# CW308T_87C51_CPU.net
KiCad netlist of a schematic drawn in Altium Designer
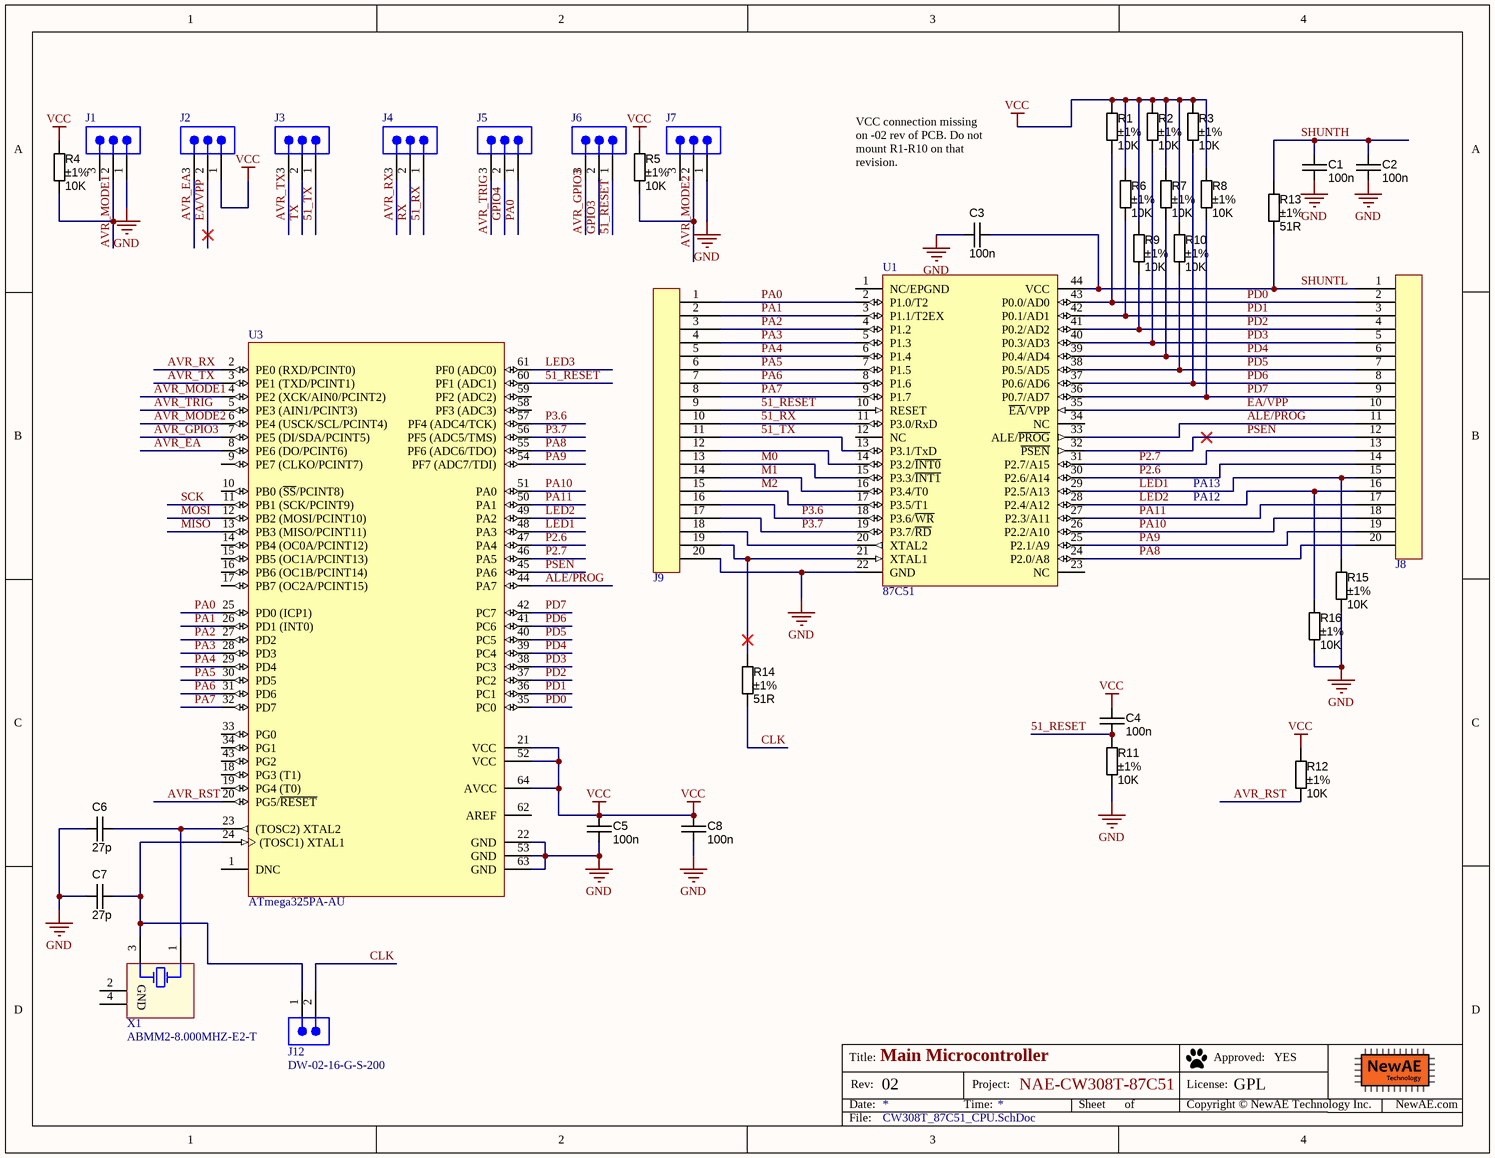
[diagram p0: CW308T_87C51_CPU.SchDoc]

(export (version "E")
  (design (tool "Eeschema 10.0.6"))
  (components
    (comp (ref "C1")
      (value "100n")
      (footprint "CAPC1608X90N")
      (description "Capacitor SMD Cer 100nF 10% 50V X7R 0603")
      (fields (field (name "TOLERANCE") "±10%") (field (name "Comment") "approved sub OK"))
      (libsource (lib "PBL - Capacitors") (part "CAPC_100n_0603_X7R_50V_10%"))
    )
    (comp (ref "C2")
      (value "100n")
      (footprint "CAPC1608X90N")
      (description "Capacitor SMD Cer 100nF 10% 50V X7R 0603")
      (fields (field (name "TOLERANCE") "±10%") (field (name "Comment") "approved sub OK"))
      (libsource (lib "PBL - Capacitors") (part "CAPC_100n_0603_X7R_50V_10%"))
    )
    (comp (ref "C3")
      (value "100n")
      (footprint "CAPC1608X90N")
      (description "Capacitor SMD Cer 100nF 10% 50V X7R 0603")
      (fields (field (name "TOLERANCE") "±10%") (field (name "Comment") "approved sub OK"))
      (libsource (lib "PBL - Capacitors") (part "CAPC_100n_0603_X7R_50V_10%"))
    )
    (comp (ref "C4")
      (value "100n")
      (footprint "CAPC1608X90N")
      (description "Capacitor SMD Cer 100nF 10% 50V X7R 0603")
      (fields (field (name "TOLERANCE") "±10%") (field (name "Comment") "approved sub OK"))
      (libsource (lib "PBL - Capacitors") (part "CAPC_100n_0603_X7R_50V_10%"))
    )
    (comp (ref "C5")
      (value "100n")
      (footprint "CAPC1608X90N")
      (description "Capacitor SMD Cer 100nF 10% 50V X7R 0603")
      (fields (field (name "TOLERANCE") "±10%") (field (name "Comment") "approved sub OK"))
      (libsource (lib "PBL - Capacitors") (part "CAPC_100n_0603_X7R_50V_10%"))
    )
    (comp (ref "C6")
      (value "27p")
      (footprint "CAPC1608X90N")
      (description "Capacitor SMD Cer 27pF 1% 100V NP0 0603")
      (fields (field (name "TOLERANCE") "±1%"))
      (libsource (lib "PBL - Capacitors") (part "CAPC_27p_0603_NP0_100V_1%"))
    )
    (comp (ref "C7")
      (value "27p")
      (footprint "CAPC1608X90N")
      (description "Capacitor SMD Cer 27pF 1% 100V NP0 0603")
      (fields (field (name "TOLERANCE") "±1%"))
      (libsource (lib "PBL - Capacitors") (part "CAPC_27p_0603_NP0_100V_1%"))
    )
    (comp (ref "C8")
      (value "100n")
      (footprint "CAPC1608X90N")
      (description "Capacitor SMD Cer 100nF 10% 50V X7R 0603")
      (fields (field (name "TOLERANCE") "±10%") (field (name "Comment") "approved sub OK"))
      (libsource (lib "PBL - Capacitors") (part "CAPC_100n_0603_X7R_50V_10%"))
    )
    (comp (ref "J1")
      (value "68000-203HLF")
      (footprint "SMTC-TSW-103-07-X-S")
      (fields (field (name "MANUFACTURER") "Samtec"))
      (libsource (lib "Altium Content Vault") (part "CMP-1024-00333-1"))
    )
    (comp (ref "J2")
      (value "68000-203HLF")
      (footprint "SMTC-TSW-103-07-X-S")
      (fields (field (name "MANUFACTURER") "Samtec"))
      (libsource (lib "Altium Content Vault") (part "CMP-1024-00333-1"))
    )
    (comp (ref "J3")
      (value "68000-203HLF")
      (footprint "SMTC-TSW-103-07-X-S")
      (fields (field (name "MANUFACTURER") "Samtec"))
      (libsource (lib "Altium Content Vault") (part "CMP-1024-00333-1"))
    )
    (comp (ref "J4")
      (value "68000-203HLF")
      (footprint "SMTC-TSW-103-07-X-S")
      (fields (field (name "MANUFACTURER") "Samtec"))
      (libsource (lib "Altium Content Vault") (part "CMP-1024-00333-1"))
    )
    (comp (ref "J5")
      (value "68000-203HLF")
      (footprint "SMTC-TSW-103-07-X-S")
      (fields (field (name "MANUFACTURER") "Samtec"))
      (libsource (lib "Altium Content Vault") (part "CMP-1024-00333-1"))
    )
    (comp (ref "J6")
      (value "68000-203HLF")
      (footprint "SMTC-TSW-103-07-X-S")
      (fields (field (name "MANUFACTURER") "Samtec"))
      (libsource (lib "Altium Content Vault") (part "CMP-1024-00333-1"))
    )
    (comp (ref "J7")
      (value "68000-203HLF")
      (footprint "SMTC-TSW-103-07-X-S")
      (fields (field (name "MANUFACTURER") "Samtec"))
      (libsource (lib "Altium Content Vault") (part "CMP-1024-00333-1"))
    )
    (comp (ref "J8")
      (value "20-Pin Header")
      (footprint "801-87-020-10-001101")
      (description "1x20 Header, Machined")
      (libsource (lib "NewAE_AltiumLib") (part "801-87-020-10-001101"))
    )
    (comp (ref "J9")
      (value "20-Pin Header")
      (footprint "801-87-020-10-001101")
      (description "1x20 Header, Machined")
      (libsource (lib "") (part "801-87-020-10-001101_1"))
    )
    (comp (ref "J12")
      (value "DW-02-16-G-S-200")
      (footprint "SMTC-DW-02-16-X-S-200")
      (fields (field (name "MANUFACTURER") "Samtec"))
      (libsource (lib "Altium Content Vault") (part "SMTC-DW-02-16-X-S-200"))
    )
    (comp (ref "R1")
      (value "10K")
      (footprint "RESC1608X55N")
      (description "Resistor SMD chip 10k Ohm 0.1W 1% 0603")
      (fields (field (name "TOLERANCE") "±1%") (field (name "Comment") "Thick Film"))
      (libsource (lib "PBL - Resistors") (part "RES_10K_0603_1%"))
    )
    (comp (ref "R2")
      (value "10K")
      (footprint "RESC1608X55N")
      (description "Resistor SMD chip 10k Ohm 0.1W 1% 0603")
      (fields (field (name "TOLERANCE") "±1%") (field (name "Comment") "Thick Film"))
      (libsource (lib "PBL - Resistors") (part "RES_10K_0603_1%"))
    )
    (comp (ref "R3")
      (value "10K")
      (footprint "RESC1608X55N")
      (description "Resistor SMD chip 10k Ohm 0.1W 1% 0603")
      (fields (field (name "TOLERANCE") "±1%") (field (name "Comment") "Thick Film"))
      (libsource (lib "PBL - Resistors") (part "RES_10K_0603_1%"))
    )
    (comp (ref "R4")
      (value "10K")
      (footprint "RESC1608X55N")
      (description "Resistor SMD chip 10k Ohm 0.1W 1% 0603")
      (fields (field (name "TOLERANCE") "±1%") (field (name "Comment") "Thick Film"))
      (libsource (lib "PBL - Resistors") (part "RES_10K_0603_1%"))
    )
    (comp (ref "R5")
      (value "10K")
      (footprint "RESC1608X55N")
      (description "Resistor SMD chip 10k Ohm 0.1W 1% 0603")
      (fields (field (name "TOLERANCE") "±1%") (field (name "Comment") "Thick Film"))
      (libsource (lib "") (part "RES_10K_0603_1%_1"))
    )
    (comp (ref "R6")
      (value "10K")
      (footprint "RESC1608X55N")
      (description "Resistor SMD chip 10k Ohm 0.1W 1% 0603")
      (fields (field (name "TOLERANCE") "±1%") (field (name "Comment") "Thick Film"))
      (libsource (lib "PBL - Resistors") (part "RES_10K_0603_1%"))
    )
    (comp (ref "R7")
      (value "10K")
      (footprint "RESC1608X55N")
      (description "Resistor SMD chip 10k Ohm 0.1W 1% 0603")
      (fields (field (name "TOLERANCE") "±1%") (field (name "Comment") "Thick Film"))
      (libsource (lib "PBL - Resistors") (part "RES_10K_0603_1%"))
    )
    (comp (ref "R8")
      (value "10K")
      (footprint "RESC1608X55N")
      (description "Resistor SMD chip 10k Ohm 0.1W 1% 0603")
      (fields (field (name "TOLERANCE") "±1%") (field (name "Comment") "Thick Film"))
      (libsource (lib "PBL - Resistors") (part "RES_10K_0603_1%"))
    )
    (comp (ref "R9")
      (value "10K")
      (footprint "RESC1608X55N")
      (description "Resistor SMD chip 10k Ohm 0.1W 1% 0603")
      (fields (field (name "TOLERANCE") "±1%") (field (name "Comment") "Thick Film"))
      (libsource (lib "PBL - Resistors") (part "RES_10K_0603_1%"))
    )
    (comp (ref "R10")
      (value "10K")
      (footprint "RESC1608X55N")
      (description "Resistor SMD chip 10k Ohm 0.1W 1% 0603")
      (fields (field (name "TOLERANCE") "±1%") (field (name "Comment") "Thick Film"))
      (libsource (lib "PBL - Resistors") (part "RES_10K_0603_1%"))
    )
    (comp (ref "R11")
      (value "10K")
      (footprint "RESC1608X55N")
      (description "Resistor SMD chip 10k Ohm 0.1W 1% 0603")
      (fields (field (name "TOLERANCE") "±1%") (field (name "Comment") "Thick Film"))
      (libsource (lib "PBL - Resistors") (part "RES_10K_0603_1%"))
    )
    (comp (ref "R12")
      (value "10K")
      (footprint "RESC1608X55N")
      (description "Resistor SMD chip 10k Ohm 0.1W 1% 0603")
      (fields (field (name "TOLERANCE") "±1%") (field (name "Comment") "Thick Film"))
      (libsource (lib "PBL - Resistors") (part "RES_10K_0603_1%"))
    )
    (comp (ref "R13")
      (value "51R")
      (footprint "RESC1608X55N")
      (description "Resistor SMD chip 51 Ohm 0.1W 1% 0603")
      (fields (field (name "TOLERANCE") "±1%") (field (name "Comment") "Thick Film"))
      (libsource (lib "PBL - Resistors") (part "RES_51R_0603_1%"))
    )
    (comp (ref "R14")
      (value "51R")
      (footprint "RESC1608X55N")
      (description "Resistor SMD chip 51 Ohm 0.1W 1% 0603")
      (fields (field (name "TOLERANCE") "±1%") (field (name "Comment") "Thick Film"))
      (libsource (lib "PBL - Resistors") (part "RES_51R_0603_1%"))
    )
    (comp (ref "R15")
      (value "10K")
      (footprint "RESC1608X55N")
      (description "Resistor SMD chip 10k Ohm 0.1W 1% 0603")
      (fields (field (name "TOLERANCE") "±1%") (field (name "Comment") "Thick Film"))
      (libsource (lib "PBL - Resistors") (part "RES_10K_0603_1%"))
    )
    (comp (ref "R16")
      (value "10K")
      (footprint "RESC1608X55N")
      (description "Resistor SMD chip 10k Ohm 0.1W 1% 0603")
      (fields (field (name "TOLERANCE") "±1%") (field (name "Comment") "Thick Film"))
      (libsource (lib "PBL - Resistors") (part "RES_10K_0603_1%"))
    )
    (comp (ref "U1")
      (value "87C51")
      (footprint "NewAE_AltiumLib:PLCC44_SOCKET")
      (libsource (lib "NewAE_AltiumLib") (part "87C51"))
    )
    (comp (ref "U3")
      (value "ATmega325PA-AU")
      (footprint "64A_M")
      (libsource (lib "Altium Content Vault") (part "MC-8B-ATM165-SQ64"))
    )
    (comp (ref "X1")
      (value "ABMM2-8.000MHZ-E2-T")
      (footprint "ABRA-ABMM2-4_V")
      (fields (field (name "MANUFACTURER") "Abracon"))
      (libsource (lib "Altium Content Vault") (part "ABRA-XTAL_1-3-4"))
    )
  )
  (nets
    (net (code "1") (name "/51_RESET") (class "Default")
      (node (ref "C4") (pin "2") (pintype "passive"))
      (node (ref "J6") (pin "1") (pinfunction "1_1") (pintype "passive"))
      (node (ref "J9") (pin "9") (pintype "passive"))
      (node (ref "R11") (pin "1") (pinfunction "1_1") (pintype "passive"))
      (node (ref "U1") (pin "10") (pinfunction "RESET_10") (pintype "input"))
      (node (ref "U3") (pin "60") (pinfunction "PF1_(ADC1)_60") (pintype "bidirectional"))
    )
    (net (code "2") (name "/51_RX") (class "Default")
      (node (ref "J4") (pin "1") (pinfunction "1_1") (pintype "passive"))
      (node (ref "J9") (pin "10") (pintype "passive"))
      (node (ref "U1") (pin "11") (pinfunction "P3.0/RxD_11") (pintype "bidirectional"))
    )
    (net (code "3") (name "/51_TX") (class "Default")
      (node (ref "J3") (pin "1") (pinfunction "1_1") (pintype "passive"))
      (node (ref "J9") (pin "11") (pintype "passive"))
      (node (ref "U1") (pin "13") (pinfunction "P3.1/TxD_13") (pintype "bidirectional"))
    )
    (net (code "4") (name "/ALE{slash}PROG") (class "Default")
      (node (ref "J8") (pin "11") (pintype "passive"))
      (node (ref "U1") (pin "33") (pinfunction "ALE/~{PROG}_33") (pintype "output"))
      (node (ref "U3") (pin "44") (pinfunction "PA7_44") (pintype "bidirectional"))
    )
    (net (code "5") (name "/AVR_EA") (class "Default")
      (node (ref "J2") (pin "3") (pinfunction "3_3") (pintype "passive"))
      (node (ref "U3") (pin "8") (pinfunction "PE6_(DO/PCINT6)_8") (pintype "bidirectional"))
    )
    (net (code "6") (name "/AVR_GPIO3") (class "Default")
      (node (ref "J6") (pin "3") (pinfunction "3_3") (pintype "passive"))
      (node (ref "U3") (pin "7") (pinfunction "PE5_(DI/SDA/PCINT5)_7") (pintype "bidirectional"))
    )
    (net (code "7") (name "/AVR_MODE1") (class "Default")
      (node (ref "J1") (pin "2") (pinfunction "2_2") (pintype "passive"))
      (node (ref "R4") (pin "2") (pinfunction "2_2") (pintype "passive"))
      (node (ref "U3") (pin "4") (pinfunction "PE2_(XCK/AIN0/PCINT2)_4") (pintype "bidirectional"))
    )
    (net (code "8") (name "/AVR_MODE2") (class "Default")
      (node (ref "J7") (pin "2") (pinfunction "2_2") (pintype "passive"))
      (node (ref "R5") (pin "1") (pinfunction "1_1") (pintype "passive"))
      (node (ref "U3") (pin "6") (pinfunction "PE4_(USCK/SCL/PCINT4)_6") (pintype "bidirectional"))
    )
    (net (code "9") (name "/AVR_RST") (class "Default")
      (node (ref "R12") (pin "2") (pinfunction "2_2") (pintype "passive"))
      (node (ref "U3") (pin "20") (pinfunction "PG5/~{RESET}_20") (pintype "bidirectional"))
    )
    (net (code "10") (name "/AVR_RX") (class "Default")
      (node (ref "J4") (pin "3") (pinfunction "3_3") (pintype "passive"))
      (node (ref "U3") (pin "2") (pinfunction "PE0_(RXD/PCINT0)_2") (pintype "bidirectional"))
    )
    (net (code "11") (name "/AVR_TRIG") (class "Default")
      (node (ref "J5") (pin "3") (pinfunction "3_3") (pintype "passive"))
      (node (ref "U3") (pin "5") (pinfunction "PE3_(AIN1/PCINT3)_5") (pintype "bidirectional"))
    )
    (net (code "12") (name "/AVR_TX") (class "Default")
      (node (ref "J3") (pin "3") (pinfunction "3_3") (pintype "passive"))
      (node (ref "U3") (pin "3") (pinfunction "PE1_(TXD/PCINT1)_3") (pintype "bidirectional"))
    )
    (net (code "13") (name "/CLK") (class "Default")
      (node (ref "J12") (pin "2") (pinfunction "2_2") (pintype "passive"))
      (node (ref "R14") (pin "2") (pinfunction "2_2") (pintype "passive"))
    )
    (net (code "14") (name "/EA{slash}VPP") (class "Default")
      (node (ref "J2") (pin "2") (pinfunction "2_2") (pintype "passive"))
      (node (ref "J8") (pin "10") (pintype "passive"))
      (node (ref "U1") (pin "35") (pinfunction "~{EA}/VPP_35") (pintype "input"))
    )
    (net (code "15") (name "/GPIO3") (class "Default")
      (node (ref "J6") (pin "2") (pinfunction "2_2") (pintype "passive"))
    )
    (net (code "16") (name "/GPIO4") (class "Default")
      (node (ref "J5") (pin "2") (pinfunction "2_2") (pintype "passive"))
    )
    (net (code "17") (name "/LED1") (class "Default")
      (node (ref "J8") (pin "15") (pintype "passive"))
      (node (ref "R15") (pin "1") (pinfunction "1_1") (pintype "passive"))
      (node (ref "U1") (pin "29") (pinfunction "P2.5/A13_29") (pintype "bidirectional"))
      (node (ref "U3") (pin "48") (pinfunction "PA3_48") (pintype "bidirectional"))
    )
    (net (code "18") (name "/LED2") (class "Default")
      (node (ref "J8") (pin "16") (pintype "passive"))
      (node (ref "R16") (pin "1") (pinfunction "1_1") (pintype "passive"))
      (node (ref "U1") (pin "28") (pinfunction "P2.4/A12_28") (pintype "bidirectional"))
      (node (ref "U3") (pin "49") (pinfunction "PA2_49") (pintype "bidirectional"))
    )
    (net (code "19") (name "/LED3") (class "Default")
      (node (ref "U3") (pin "61") (pinfunction "PF0_(ADC0)_61") (pintype "bidirectional"))
    )
    (net (code "20") (name "/M0") (class "Default")
      (node (ref "J9") (pin "13") (pintype "passive"))
      (node (ref "U1") (pin "15") (pinfunction "P3.3/~{INT1}_15") (pintype "bidirectional"))
    )
    (net (code "21") (name "/M1") (class "Default")
      (node (ref "J9") (pin "14") (pintype "passive"))
      (node (ref "U1") (pin "16") (pinfunction "P3.4/T0_16") (pintype "bidirectional"))
    )
    (net (code "22") (name "/M2") (class "Default")
      (node (ref "J9") (pin "15") (pintype "passive"))
      (node (ref "U1") (pin "17") (pinfunction "P3.5/T1_17") (pintype "bidirectional"))
    )
    (net (code "23") (name "/MISO") (class "Default")
      (node (ref "U3") (pin "13") (pinfunction "PB3_(MISO/PCINT11)_13") (pintype "bidirectional"))
    )
    (net (code "24") (name "/MOSI") (class "Default")
      (node (ref "U3") (pin "12") (pinfunction "PB2_(MOSI/PCINT10)_12") (pintype "bidirectional"))
    )
    (net (code "25") (name "/P2.6") (class "Default")
      (node (ref "J8") (pin "14") (pintype "passive"))
      (node (ref "U1") (pin "30") (pinfunction "P2.6/A14_30") (pintype "bidirectional"))
      (node (ref "U3") (pin "47") (pinfunction "PA4_47") (pintype "bidirectional"))
    )
    (net (code "26") (name "/P2.7") (class "Default")
      (node (ref "J8") (pin "13") (pintype "passive"))
      (node (ref "U1") (pin "31") (pinfunction "P2.7/A15_31") (pintype "bidirectional"))
      (node (ref "U3") (pin "46") (pinfunction "PA5_46") (pintype "bidirectional"))
    )
    (net (code "27") (name "/P3.6") (class "Default")
      (node (ref "J9") (pin "16") (pintype "passive"))
      (node (ref "U1") (pin "18") (pinfunction "P3.6/~{WR}_18") (pintype "bidirectional"))
      (node (ref "U3") (pin "57") (pinfunction "PF4_(ADC4/TCK)_57") (pintype "bidirectional"))
    )
    (net (code "28") (name "/P3.7") (class "Default")
      (node (ref "J9") (pin "17") (pintype "passive"))
      (node (ref "U1") (pin "19") (pinfunction "P3.7/~{RD}_19") (pintype "bidirectional"))
      (node (ref "U3") (pin "56") (pinfunction "PF5_(ADC5/TMS)_56") (pintype "bidirectional"))
    )
    (net (code "29") (name "/PA0") (class "Default")
      (node (ref "J5") (pin "1") (pinfunction "1_1") (pintype "passive"))
      (node (ref "J9") (pin "1") (pintype "passive"))
      (node (ref "U1") (pin "2") (pinfunction "P1.0/T2_2") (pintype "bidirectional"))
      (node (ref "U3") (pin "25") (pinfunction "PD0_(ICP1)_25") (pintype "bidirectional"))
    )
    (net (code "30") (name "/PA1") (class "Default")
      (node (ref "J9") (pin "2") (pintype "passive"))
      (node (ref "U1") (pin "3") (pinfunction "P1.1/T2EX_3") (pintype "bidirectional"))
      (node (ref "U3") (pin "26") (pinfunction "PD1_(INT0)_26") (pintype "bidirectional"))
    )
    (net (code "31") (name "/PA2") (class "Default")
      (node (ref "J9") (pin "3") (pintype "passive"))
      (node (ref "U1") (pin "4") (pinfunction "P1.2_4") (pintype "bidirectional"))
      (node (ref "U3") (pin "27") (pinfunction "PD2_27") (pintype "bidirectional"))
    )
    (net (code "32") (name "/PA3") (class "Default")
      (node (ref "J9") (pin "4") (pintype "passive"))
      (node (ref "U1") (pin "5") (pinfunction "P1.3_5") (pintype "bidirectional"))
      (node (ref "U3") (pin "28") (pinfunction "PD3_28") (pintype "bidirectional"))
    )
    (net (code "33") (name "/PA4") (class "Default")
      (node (ref "J9") (pin "5") (pintype "passive"))
      (node (ref "U1") (pin "6") (pinfunction "P1.4_6") (pintype "bidirectional"))
      (node (ref "U3") (pin "29") (pinfunction "PD4_29") (pintype "bidirectional"))
    )
    (net (code "34") (name "/PA5") (class "Default")
      (node (ref "J9") (pin "6") (pintype "passive"))
      (node (ref "U1") (pin "7") (pinfunction "P1.5_7") (pintype "bidirectional"))
      (node (ref "U3") (pin "30") (pinfunction "PD5_30") (pintype "bidirectional"))
    )
    (net (code "35") (name "/PA6") (class "Default")
      (node (ref "J9") (pin "7") (pintype "passive"))
      (node (ref "U1") (pin "8") (pinfunction "P1.6_8") (pintype "bidirectional"))
      (node (ref "U3") (pin "31") (pinfunction "PD6_31") (pintype "bidirectional"))
    )
    (net (code "36") (name "/PA7") (class "Default")
      (node (ref "J9") (pin "8") (pintype "passive"))
      (node (ref "U1") (pin "9") (pinfunction "P1.7_9") (pintype "bidirectional"))
      (node (ref "U3") (pin "32") (pinfunction "PD7_32") (pintype "bidirectional"))
    )
    (net (code "37") (name "/PA8") (class "Default")
      (node (ref "J8") (pin "20") (pintype "passive"))
      (node (ref "U1") (pin "24") (pinfunction "P2.0/A8_24") (pintype "bidirectional"))
      (node (ref "U3") (pin "55") (pinfunction "PF6_(ADC6/TDO)_55") (pintype "bidirectional"))
    )
    (net (code "38") (name "/PA9") (class "Default")
      (node (ref "J8") (pin "19") (pintype "passive"))
      (node (ref "U1") (pin "25") (pinfunction "P2.1/A9_25") (pintype "bidirectional"))
      (node (ref "U3") (pin "54") (pinfunction "PF7_(ADC7/TDI)_54") (pintype "bidirectional"))
    )
    (net (code "39") (name "/PA10") (class "Default")
      (node (ref "J8") (pin "18") (pintype "passive"))
      (node (ref "U1") (pin "26") (pinfunction "P2.2/A10_26") (pintype "bidirectional"))
      (node (ref "U3") (pin "51") (pinfunction "PA0_51") (pintype "bidirectional"))
    )
    (net (code "40") (name "/PA11") (class "Default")
      (node (ref "J8") (pin "17") (pintype "passive"))
      (node (ref "U1") (pin "27") (pinfunction "P2.3/A11_27") (pintype "bidirectional"))
      (node (ref "U3") (pin "50") (pinfunction "PA1_50") (pintype "bidirectional"))
    )
    (net (code "41") (name "/PD0") (class "Default")
      (node (ref "J8") (pin "2") (pintype "passive"))
      (node (ref "R1") (pin "2") (pinfunction "2_2") (pintype "passive"))
      (node (ref "U1") (pin "43") (pinfunction "P0.0/AD0_43") (pintype "bidirectional"))
      (node (ref "U3") (pin "35") (pinfunction "PC0_35") (pintype "bidirectional"))
    )
    (net (code "42") (name "/PD1") (class "Default")
      (node (ref "J8") (pin "3") (pintype "passive"))
      (node (ref "R6") (pin "2") (pinfunction "2_2") (pintype "passive"))
      (node (ref "U1") (pin "42") (pinfunction "P0.1/AD1_42") (pintype "bidirectional"))
      (node (ref "U3") (pin "36") (pinfunction "PC1_36") (pintype "bidirectional"))
    )
    (net (code "43") (name "/PD2") (class "Default")
      (node (ref "J8") (pin "4") (pintype "passive"))
      (node (ref "R9") (pin "2") (pinfunction "2_2") (pintype "passive"))
      (node (ref "U1") (pin "41") (pinfunction "P0.2/AD2_41") (pintype "bidirectional"))
      (node (ref "U3") (pin "37") (pinfunction "PC2_37") (pintype "bidirectional"))
    )
    (net (code "44") (name "/PD3") (class "Default")
      (node (ref "J8") (pin "5") (pintype "passive"))
      (node (ref "R2") (pin "2") (pinfunction "2_2") (pintype "passive"))
      (node (ref "U1") (pin "40") (pinfunction "P0.3/AD3_40") (pintype "bidirectional"))
      (node (ref "U3") (pin "38") (pinfunction "PC3_38") (pintype "bidirectional"))
    )
    (net (code "45") (name "/PD4") (class "Default")
      (node (ref "J8") (pin "6") (pintype "passive"))
      (node (ref "R7") (pin "2") (pinfunction "2_2") (pintype "passive"))
      (node (ref "U1") (pin "39") (pinfunction "P0.4/AD4_39") (pintype "bidirectional"))
      (node (ref "U3") (pin "39") (pinfunction "PC4_39") (pintype "bidirectional"))
    )
    (net (code "46") (name "/PD5") (class "Default")
      (node (ref "J8") (pin "7") (pintype "passive"))
      (node (ref "R10") (pin "2") (pinfunction "2_2") (pintype "passive"))
      (node (ref "U1") (pin "38") (pinfunction "P0.5/AD5_38") (pintype "bidirectional"))
      (node (ref "U3") (pin "40") (pinfunction "PC5_40") (pintype "bidirectional"))
    )
    (net (code "47") (name "/PD6") (class "Default")
      (node (ref "J8") (pin "8") (pintype "passive"))
      (node (ref "R3") (pin "2") (pinfunction "2_2") (pintype "passive"))
      (node (ref "U1") (pin "37") (pinfunction "P0.6/AD6_37") (pintype "bidirectional"))
      (node (ref "U3") (pin "41") (pinfunction "PC6_41") (pintype "bidirectional"))
    )
    (net (code "48") (name "/PD7") (class "Default")
      (node (ref "J8") (pin "9") (pintype "passive"))
      (node (ref "R8") (pin "2") (pinfunction "2_2") (pintype "passive"))
      (node (ref "U1") (pin "36") (pinfunction "P0.7/AD7_36") (pintype "bidirectional"))
      (node (ref "U3") (pin "42") (pinfunction "PC7_42") (pintype "bidirectional"))
    )
    (net (code "49") (name "/PSEN") (class "Default")
      (node (ref "J8") (pin "12") (pintype "passive"))
      (node (ref "U1") (pin "32") (pinfunction "~{PSEN}_32") (pintype "output"))
      (node (ref "U3") (pin "45") (pinfunction "PA6_45") (pintype "bidirectional"))
    )
    (net (code "50") (name "/RX") (class "Default")
      (node (ref "J4") (pin "2") (pinfunction "2_2") (pintype "passive"))
    )
    (net (code "51") (name "/SCK") (class "Default")
      (node (ref "U3") (pin "11") (pinfunction "PB1_(SCK/PCINT9)_11") (pintype "bidirectional"))
    )
    (net (code "52") (name "/SHUNTH") (class "Default")
      (node (ref "C1") (pin "1") (pintype "passive"))
      (node (ref "C2") (pin "1") (pintype "passive"))
      (node (ref "R13") (pin "1") (pinfunction "1_1") (pintype "passive"))
    )
    (net (code "53") (name "/SHUNTL") (class "Default")
      (node (ref "C3") (pin "2") (pintype "passive"))
      (node (ref "J8") (pin "1") (pintype "passive"))
      (node (ref "R13") (pin "2") (pinfunction "2_2") (pintype "passive"))
      (node (ref "U1") (pin "44") (pinfunction "VCC_44") (pintype "power_in"))
    )
    (net (code "54") (name "/TX") (class "Default")
      (node (ref "J3") (pin "2") (pinfunction "2_2") (pintype "passive"))
    )
    (net (code "55") (name "GND") (class "Default")
      (node (ref "C1") (pin "2") (pintype "passive"))
      (node (ref "C2") (pin "2") (pintype "passive"))
      (node (ref "C3") (pin "1") (pintype "passive"))
      (node (ref "C5") (pin "2") (pintype "passive"))
      (node (ref "C6") (pin "1") (pintype "passive"))
      (node (ref "C7") (pin "1") (pintype "passive"))
      (node (ref "C8") (pin "2") (pintype "passive"))
      (node (ref "J1") (pin "1") (pinfunction "1_1") (pintype "passive"))
      (node (ref "J7") (pin "1") (pinfunction "1_1") (pintype "passive"))
      (node (ref "J9") (pin "20") (pintype "passive"))
      (node (ref "R11") (pin "2") (pinfunction "2_2") (pintype "passive"))
      (node (ref "R15") (pin "2") (pinfunction "2_2") (pintype "passive"))
      (node (ref "R16") (pin "2") (pinfunction "2_2") (pintype "passive"))
      (node (ref "U1") (pin "22") (pinfunction "GND_22") (pintype "power_in"))
      (node (ref "U3") (pin "22") (pinfunction "GND_22") (pintype "power_in"))
      (node (ref "U3") (pin "53") (pinfunction "GND_53") (pintype "power_in"))
      (node (ref "U3") (pin "63") (pinfunction "GND_63") (pintype "power_in"))
    )
    (net (code "56") (name "Net-(U1-P3.2{slash}~{INT0})") (class "Default")
      (node (ref "J9") (pin "12") (pintype "passive"))
      (node (ref "U1") (pin "14") (pinfunction "P3.2/~{INT0}_14") (pintype "bidirectional"))
    )
    (net (code "57") (name "Net-(U1-XTAL1)") (class "Default")
      (node (ref "J9") (pin "19") (pintype "passive"))
      (node (ref "R14") (pin "1") (pinfunction "1_1") (pintype "passive"))
      (node (ref "U1") (pin "21") (pinfunction "XTAL1_21") (pintype "input"))
    )
    (net (code "58") (name "Net-(U1-XTAL2)") (class "Default")
      (node (ref "J9") (pin "18") (pintype "passive"))
      (node (ref "U1") (pin "20") (pinfunction "XTAL2_20") (pintype "output"))
    )
    (net (code "59") (name "Net-(U3-(TOSC1)_XTAL1)") (class "Default")
      (node (ref "C7") (pin "2") (pintype "passive"))
      (node (ref "J12") (pin "1") (pinfunction "1_1") (pintype "passive"))
      (node (ref "U3") (pin "24") (pinfunction "(TOSC1)_XTAL1_24") (pintype "input"))
      (node (ref "X1") (pin "3") (pinfunction "X2_3") (pintype "passive"))
    )
    (net (code "60") (name "Net-(U3-(TOSC2)_XTAL2)") (class "Default")
      (node (ref "C6") (pin "2") (pintype "passive"))
      (node (ref "U3") (pin "23") (pinfunction "(TOSC2)_XTAL2_23") (pintype "output"))
      (node (ref "X1") (pin "1") (pinfunction "X1_1") (pintype "passive"))
    )
    (net (code "61") (name "VCC") (class "Default")
      (node (ref "C4") (pin "1") (pintype "passive"))
      (node (ref "C5") (pin "1") (pintype "passive"))
      (node (ref "C8") (pin "1") (pintype "passive"))
      (node (ref "J2") (pin "1") (pinfunction "1_1") (pintype "passive"))
      (node (ref "R1") (pin "1") (pinfunction "1_1") (pintype "passive"))
      (node (ref "R10") (pin "1") (pinfunction "1_1") (pintype "passive"))
      (node (ref "R12") (pin "1") (pinfunction "1_1") (pintype "passive"))
      (node (ref "R2") (pin "1") (pinfunction "1_1") (pintype "passive"))
      (node (ref "R3") (pin "1") (pinfunction "1_1") (pintype "passive"))
      (node (ref "R4") (pin "1") (pinfunction "1_1") (pintype "passive"))
      (node (ref "R5") (pin "2") (pinfunction "2_2") (pintype "passive"))
      (node (ref "R6") (pin "1") (pinfunction "1_1") (pintype "passive"))
      (node (ref "R7") (pin "1") (pinfunction "1_1") (pintype "passive"))
      (node (ref "R8") (pin "1") (pinfunction "1_1") (pintype "passive"))
      (node (ref "R9") (pin "1") (pinfunction "1_1") (pintype "passive"))
      (node (ref "U3") (pin "21") (pinfunction "VCC_21") (pintype "power_in"))
      (node (ref "U3") (pin "52") (pinfunction "VCC_52") (pintype "power_in"))
      (node (ref "U3") (pin "64") (pinfunction "AVCC_64") (pintype "power_in"))
    )
    (net (code "62") (name "unconnected-(J1-Pad3)") (class "Default")
      (node (ref "J1") (pin "3") (pinfunction "3_3") (pintype "passive"))
    )
    (net (code "63") (name "unconnected-(J7-Pad3)") (class "Default")
      (node (ref "J7") (pin "3") (pinfunction "3_3") (pintype "passive"))
    )
    (net (code "64") (name "unconnected-(U1-NC-Pad12)") (class "Default")
      (node (ref "U1") (pin "12") (pinfunction "NC_12") (pintype "tri_state"))
    )
    (net (code "65") (name "unconnected-(U1-NC-Pad23)") (class "Default")
      (node (ref "U1") (pin "23") (pinfunction "NC_23") (pintype "tri_state"))
    )
    (net (code "66") (name "unconnected-(U1-NC-Pad34)") (class "Default")
      (node (ref "U1") (pin "34") (pinfunction "NC_34") (pintype "tri_state"))
    )
    (net (code "67") (name "unconnected-(U1-NC{slash}EPGND-Pad1)") (class "Default")
      (node (ref "U1") (pin "1") (pinfunction "NC/EPGND_1") (pintype "passive"))
    )
    (net (code "68") (name "unconnected-(U3-AREF-Pad62)") (class "Default")
      (node (ref "U3") (pin "62") (pinfunction "AREF_62") (pintype "power_in"))
    )
    (net (code "69") (name "unconnected-(U3-DNC-Pad1)") (class "Default")
      (node (ref "U3") (pin "1") (pinfunction "DNC_1") (pintype "passive"))
    )
    (net (code "70") (name "unconnected-(U3-PB0_(~{SS}{slash}PCINT8)-Pad10)") (class "Default")
      (node (ref "U3") (pin "10") (pinfunction "PB0_(~{SS}/PCINT8)_10") (pintype "bidirectional"))
    )
    (net (code "71") (name "unconnected-(U3-PB4_(OC0A{slash}PCINT12)-Pad14)") (class "Default")
      (node (ref "U3") (pin "14") (pinfunction "PB4_(OC0A/PCINT12)_14") (pintype "bidirectional"))
    )
    (net (code "72") (name "unconnected-(U3-PB5_(OC1A{slash}PCINT13)-Pad15)") (class "Default")
      (node (ref "U3") (pin "15") (pinfunction "PB5_(OC1A/PCINT13)_15") (pintype "bidirectional"))
    )
    (net (code "73") (name "unconnected-(U3-PB6_(OC1B{slash}PCINT14)-Pad16)") (class "Default")
      (node (ref "U3") (pin "16") (pinfunction "PB6_(OC1B/PCINT14)_16") (pintype "bidirectional"))
    )
    (net (code "74") (name "unconnected-(U3-PB7_(OC2A{slash}PCINT15)-Pad17)") (class "Default")
      (node (ref "U3") (pin "17") (pinfunction "PB7_(OC2A/PCINT15)_17") (pintype "bidirectional"))
    )
    (net (code "75") (name "unconnected-(U3-PE7_(CLKO{slash}PCINT7)-Pad9)") (class "Default")
      (node (ref "U3") (pin "9") (pinfunction "PE7_(CLKO/PCINT7)_9") (pintype "bidirectional"))
    )
    (net (code "76") (name "unconnected-(U3-PF2_(ADC2)-Pad59)") (class "Default")
      (node (ref "U3") (pin "59") (pinfunction "PF2_(ADC2)_59") (pintype "bidirectional"))
    )
    (net (code "77") (name "unconnected-(U3-PF3_(ADC3)-Pad58)") (class "Default")
      (node (ref "U3") (pin "58") (pinfunction "PF3_(ADC3)_58") (pintype "bidirectional"))
    )
    (net (code "78") (name "unconnected-(U3-PG0-Pad33)") (class "Default")
      (node (ref "U3") (pin "33") (pinfunction "PG0_33") (pintype "bidirectional"))
    )
    (net (code "79") (name "unconnected-(U3-PG1-Pad34)") (class "Default")
      (node (ref "U3") (pin "34") (pinfunction "PG1_34") (pintype "bidirectional"))
    )
    (net (code "80") (name "unconnected-(U3-PG2-Pad43)") (class "Default")
      (node (ref "U3") (pin "43") (pinfunction "PG2_43") (pintype "bidirectional"))
    )
    (net (code "81") (name "unconnected-(U3-PG3_(T1)-Pad18)") (class "Default")
      (node (ref "U3") (pin "18") (pinfunction "PG3_(T1)_18") (pintype "bidirectional"))
    )
    (net (code "82") (name "unconnected-(U3-PG4_(T0)-Pad19)") (class "Default")
      (node (ref "U3") (pin "19") (pinfunction "PG4_(T0)_19") (pintype "bidirectional"))
    )
    (net (code "83") (name "unconnected-(X1-GND-Pad2)") (class "Default")
      (node (ref "X1") (pin "2") (pinfunction "GND_2") (pintype "power_in"))
    )
    (net (code "84") (name "unconnected-(X1-GND-Pad4)") (class "Default")
      (node (ref "X1") (pin "4") (pinfunction "GND_4") (pintype "power_in"))
    )
  )
)
